# tricorder-teensy-mk-1_11.net
KiCad netlist of a schematic drawn in EAGLE
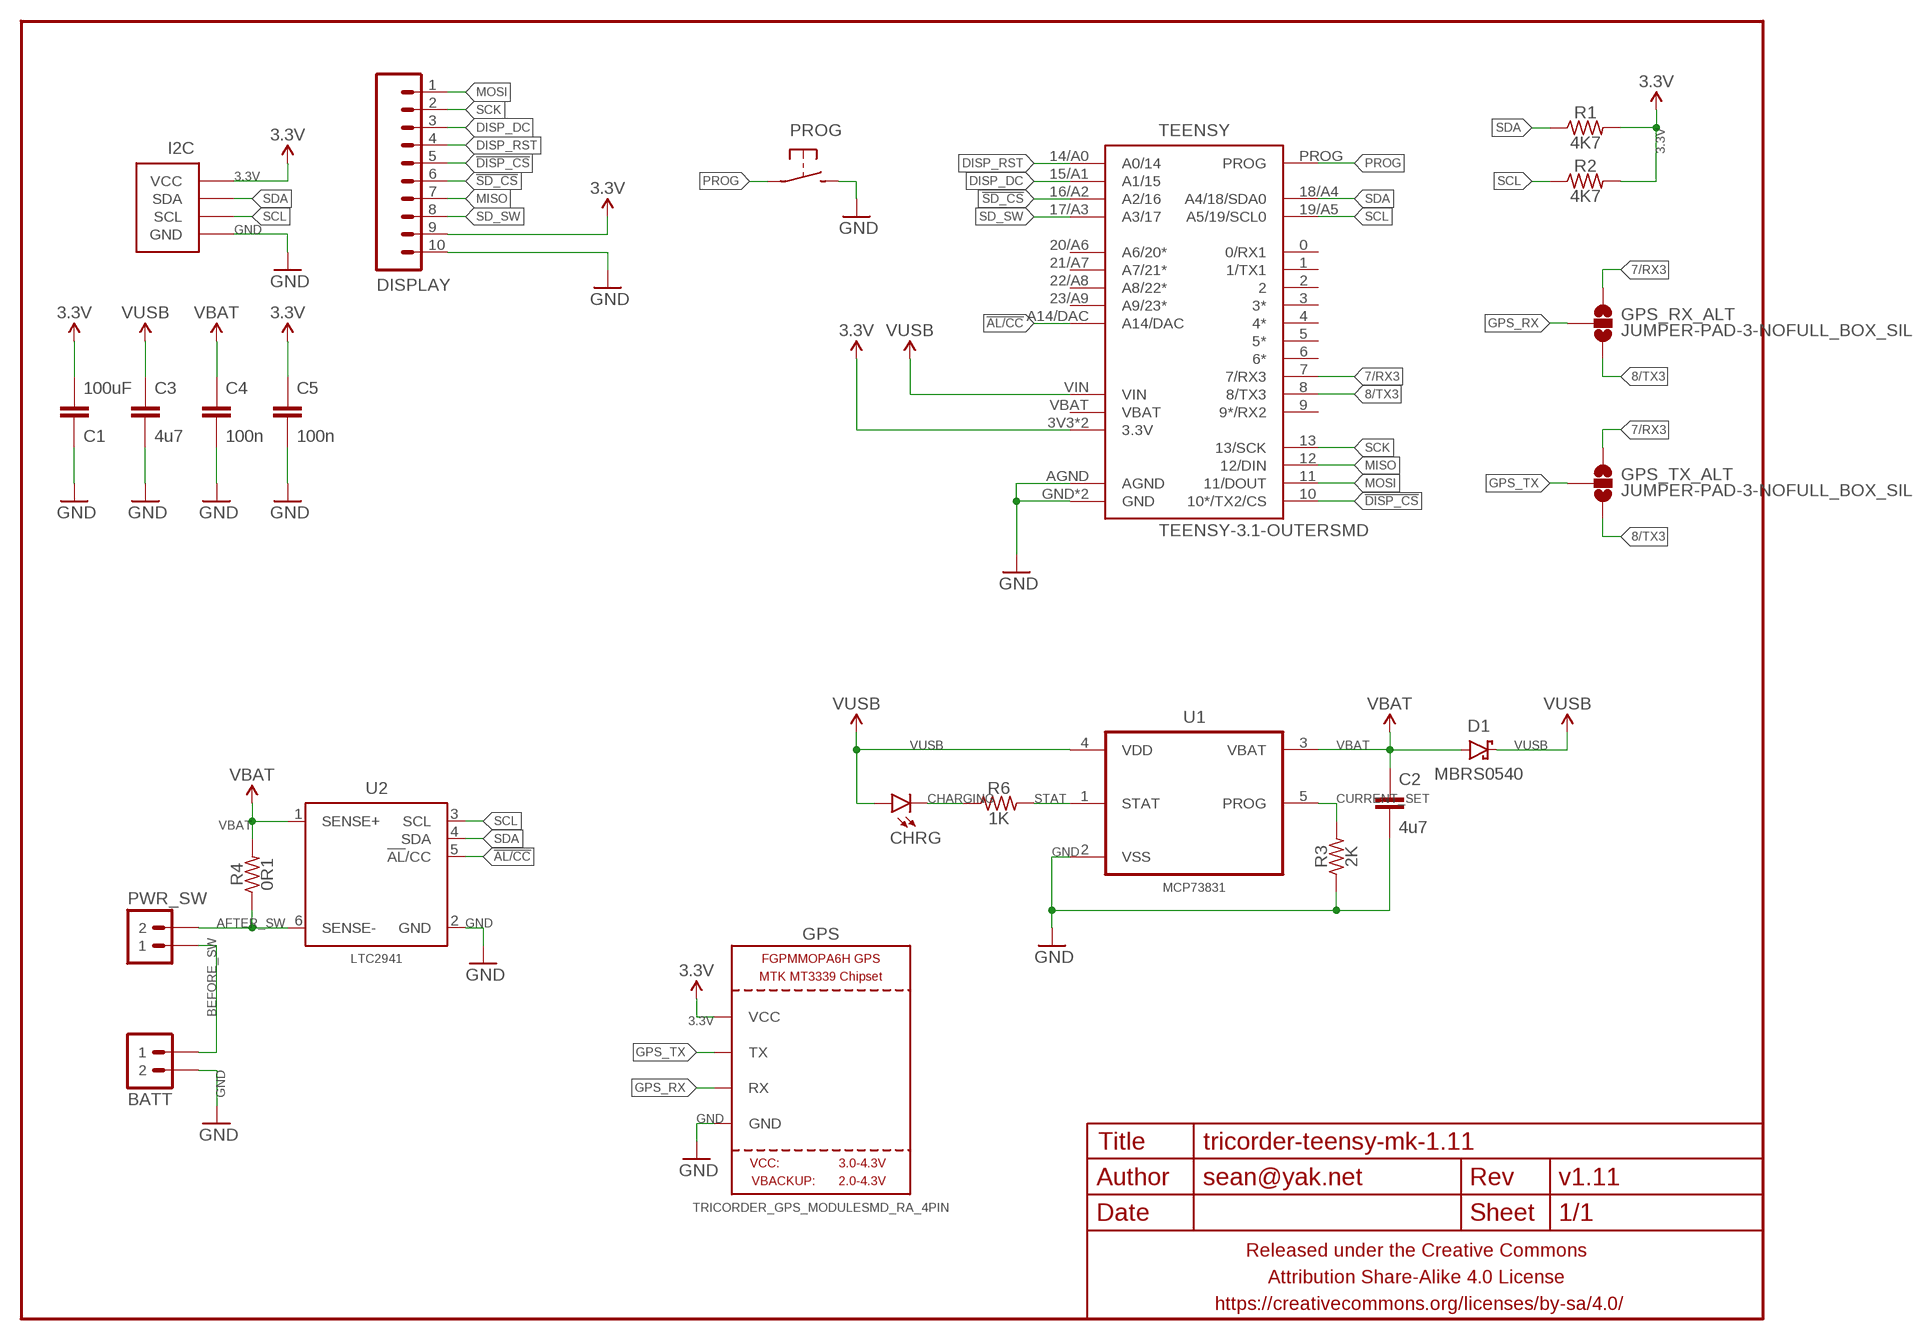
[diagram p0: schematic, sheet 1]

(export (version "E")
  (design (tool "Eeschema 10.0.6"))
  (components
    (comp (ref "BATT")
      (value "M02JST-2MM-SMT")
      (footprint "eagle-import:JST-2-SMD")
      (libsource (lib "eagle-import") (part "M02JST-2MM-SMT"))
    )
    (comp (ref "C1")
      (value "100uF")
      (footprint "eagle-import:C1210")
      (libsource (lib "eagle-import") (part "CAPACITOR-CERAMICC1210"))
    )
    (comp (ref "C2")
      (value "4u7")
      (footprint "eagle-import:C0603-TIGHTER")
      (libsource (lib "eagle-import") (part "CAPACITOR-CERAMICC0603-TIGHTER"))
    )
    (comp (ref "C3")
      (value "4u7")
      (footprint "eagle-import:C0603-TIGHTER")
      (libsource (lib "eagle-import") (part "CAPACITOR-CERAMICC0603-TIGHTER"))
    )
    (comp (ref "C4")
      (value "100n")
      (footprint "eagle-import:C0603-TIGHTER")
      (libsource (lib "eagle-import") (part "CAPACITOR-CERAMICC0603-TIGHTER"))
    )
    (comp (ref "C5")
      (value "100n")
      (footprint "eagle-import:C0603-TIGHTER")
      (libsource (lib "eagle-import") (part "CAPACITOR-CERAMICC0603-TIGHTER"))
    )
    (comp (ref "CHRG")
      (value "LED0603-TIGHT")
      (footprint "eagle-import:LED-0603-TIGHT")
      (libsource (lib "eagle-import") (part "LED0603-TIGHT"))
    )
    (comp (ref "D1")
      (value "MBRS0540")
      (footprint "eagle-import:SOD123-SCHOTTKY")
      (libsource (lib "eagle-import") (part "DIODE-SCHOTTKYSOD123"))
    )
    (comp (ref "DISPLAY")
      (value "M10SMD_RA_2MM")
      (footprint "eagle-import:1X10_SMD_RA_MALE")
      (libsource (lib "eagle-import") (part "M10SMD_RA_2MM"))
    )
    (comp (ref "FRAME1")
      (value "FRAME-LETTERNO_PACKAGE")
      (footprint "eagle-import:DUMMY")
      (fields
        (field (name "DESIGNER") "sean@yak.net")
        (field (name "VERSION") "v1.11")
        (field (name "DESIGNER_1") "sean@yak.net")
        (field (name "VERSION_1") "v1.11")
      )
      (libsource (lib "eagle-import") (part "FRAME-LETTERNO_PACKAGE"))
    )
    (comp (ref "GPS")
      (value "TRICORDER_GPS_MODULESMD_RA_4PIN")
      (footprint "eagle-import:TRICORDER_GPS_MODULE_RA_CONN_SMD_4PIN")
      (libsource (lib "eagle-import") (part "TRICORDER_GPS_MODULESMD_RA_4PIN"))
    )
    (comp (ref "GPS_RX_ALT")
      (value "JUMPER-PAD-3-NOFULL_BOX_SILK")
      (footprint "eagle-import:PAD-JUMPER-3-NO_YES_SILK_FULL_BOX")
      (libsource (lib "eagle-import") (part "JUMPER-PAD-3-NOFULL_BOX_SILK"))
    )
    (comp (ref "GPS_TX_ALT")
      (value "JUMPER-PAD-3-NOFULL_BOX_SILK")
      (footprint "eagle-import:PAD-JUMPER-3-NO_YES_SILK_FULL_BOX")
      (libsource (lib "eagle-import") (part "JUMPER-PAD-3-NOFULL_BOX_SILK"))
    )
    (comp (ref "I2C")
      (value "M04-I2CSMD_2MM_RA")
      (footprint "eagle-import:1X04_SMD_RA_2MM_I2C")
      (libsource (lib "eagle-import") (part "M04-I2CSMD_2MM_RA"))
    )
    (comp (ref "PROG")
      (value "SPST-NO-TACTCK-PTS840-GK")
      (footprint "eagle-import:TACTILE-SMD-CK-PTS840-GK")
      (libsource (lib "eagle-import") (part "SPST-NO-TACTCK-PTS840-GK"))
    )
    (comp (ref "PWR_SW")
      (value "M02JST-2MM-SMT")
      (footprint "eagle-import:JST-2-SMD")
      (libsource (lib "eagle-import") (part "M02JST-2MM-SMT"))
    )
    (comp (ref "R1")
      (value "4K7")
      (footprint "eagle-import:R0603-TIGHTER")
      (libsource (lib "eagle-import") (part "RESISTORR0603-TIGHTER"))
    )
    (comp (ref "R2")
      (value "4K7")
      (footprint "eagle-import:R0603-TIGHTER")
      (libsource (lib "eagle-import") (part "RESISTORR0603-TIGHTER"))
    )
    (comp (ref "R3")
      (value "2K")
      (footprint "eagle-import:R0603-TIGHTER")
      (libsource (lib "eagle-import") (part "RESISTORR0603-TIGHTER"))
    )
    (comp (ref "R4")
      (value "0R1")
      (footprint "eagle-import:R0805-TIGHTER")
      (libsource (lib "eagle-import") (part "RESISTORR0805-TIGHTER"))
    )
    (comp (ref "R6")
      (value "1K")
      (footprint "eagle-import:R0603-TIGHTER")
      (libsource (lib "eagle-import") (part "RESISTORR0603-TIGHTER"))
    )
    (comp (ref "TEENSY")
      (value "TEENSY-3.1-OUTERSMD")
      (footprint "eagle-import:TEENSY-3.1_SMT_BOTTOM_OUTERONLY")
      (libsource (lib "eagle-import") (part "TEENSY-3.1-OUTERSMD"))
    )
    (comp (ref "U1")
      (value "MCP73831")
      (footprint "eagle-import:SOT95P280X145-5N")
      (fields (field (name "MPN") "MCP73831T-2ACI/OT"))
      (libsource (lib "eagle-import") (part "MCP73831T-2ACI/OT"))
    )
    (comp (ref "U2")
      (value "LTC2941")
      (footprint "eagle-import:DFN200X300X50-7N")
      (libsource (lib "eagle-import") (part "LTC2941/2DCB"))
    )
  )
  (nets
    (net (code "1") (name "/AFTER_SW") (class "Default")
      (node (ref "PWR_SW") (pin "1") (pinfunction "2_1") (pintype "passive"))
      (node (ref "R4") (pin "1") (pinfunction "1_1") (pintype "passive"))
      (node (ref "U2") (pin "6") (pinfunction "SENSE-_6") (pintype "bidirectional"))
    )
    (net (code "2") (name "/BEFORE_SW") (class "Default")
      (node (ref "BATT") (pin "2") (pinfunction "1_2") (pintype "passive"))
      (node (ref "PWR_SW") (pin "2") (pinfunction "1_2") (pintype "passive"))
    )
    (net (code "3") (name "/CHARGING") (class "Default")
      (node (ref "CHRG") (pin "C") (pinfunction "C_C") (pintype "passive"))
      (node (ref "R6") (pin "1") (pinfunction "1_1") (pintype "passive"))
    )
    (net (code "4") (name "/CURRENT_SET") (class "Default")
      (node (ref "R3") (pin "2") (pinfunction "2_2") (pintype "passive"))
      (node (ref "U1") (pin "5") (pinfunction "PROG_5") (pintype "input"))
    )
    (net (code "5") (name "/STAT") (class "Default")
      (node (ref "R6") (pin "2") (pinfunction "2_2") (pintype "passive"))
      (node (ref "U1") (pin "1") (pinfunction "STAT_1") (pintype "output"))
    )
    (net (code "6") (name "/~{AL{slash}CC}") (class "Default")
      (node (ref "TEENSY") (pin "A14/DAC") (pinfunction "A14/DAC_A14/DAC") (pintype "bidirectional"))
      (node (ref "U2") (pin "5") (pinfunction "~{AL}/CC_5") (pintype "bidirectional"))
    )
    (net (code "7") (name "/~{DISP_CS}") (class "Default")
      (node (ref "DISPLAY") (pin "5") (pinfunction "5_5") (pintype "passive"))
      (node (ref "TEENSY") (pin "10") (pinfunction "10*/TX2/CS_10") (pintype "bidirectional"))
    )
    (net (code "8") (name "/~{SD_CS}") (class "Default")
      (node (ref "DISPLAY") (pin "6") (pinfunction "6_6") (pintype "passive"))
      (node (ref "TEENSY") (pin "16/A2") (pinfunction "A2/16_16/A2") (pintype "bidirectional"))
    )
    (net (code "9") (name "3.3V") (class "Default")
      (node (ref "C1") (pin "2") (pinfunction "2_2") (pintype "passive"))
      (node (ref "C5") (pin "1") (pinfunction "1_1") (pintype "passive"))
      (node (ref "DISPLAY") (pin "9") (pinfunction "9_9") (pintype "passive"))
      (node (ref "GPS") (pin "VCC") (pinfunction "VCC_VCC") (pintype "bidirectional"))
      (node (ref "I2C") (pin "VCC") (pinfunction "VCC_VCC") (pintype "bidirectional"))
      (node (ref "R1") (pin "2") (pinfunction "2_2") (pintype "passive"))
      (node (ref "R2") (pin "2") (pinfunction "2_2") (pintype "passive"))
      (node (ref "TEENSY") (pin "3V3") (pinfunction "3.3V_3V3") (pintype "bidirectional"))
      (node (ref "TEENSY") (pin "3V3@1") (pinfunction "3.3V_3V3@1") (pintype "bidirectional"))
    )
    (net (code "10") (name "7{slash}RX3") (class "Default")
      (node (ref "GPS_RX_ALT") (pin "1") (pinfunction "1_1") (pintype "passive"))
      (node (ref "GPS_TX_ALT") (pin "1") (pinfunction "1_1") (pintype "passive"))
      (node (ref "TEENSY") (pin "7") (pinfunction "7/RX3_7") (pintype "bidirectional"))
    )
    (net (code "11") (name "8{slash}TX3") (class "Default")
      (node (ref "GPS_RX_ALT") (pin "3") (pinfunction "3_3") (pintype "passive"))
      (node (ref "GPS_TX_ALT") (pin "3") (pinfunction "3_3") (pintype "passive"))
      (node (ref "TEENSY") (pin "8") (pinfunction "8/TX3_8") (pintype "bidirectional"))
    )
    (net (code "12") (name "DISP_DC") (class "Default")
      (node (ref "DISPLAY") (pin "3") (pinfunction "3_3") (pintype "passive"))
      (node (ref "TEENSY") (pin "15/A1") (pinfunction "A1/15_15/A1") (pintype "bidirectional"))
    )
    (net (code "13") (name "DISP_RST") (class "Default")
      (node (ref "DISPLAY") (pin "4") (pinfunction "4_4") (pintype "passive"))
      (node (ref "TEENSY") (pin "14/A0") (pinfunction "A0/14_14/A0") (pintype "bidirectional"))
    )
    (net (code "14") (name "GND") (class "Default")
      (node (ref "BATT") (pin "1") (pinfunction "2_1") (pintype "passive"))
      (node (ref "C1") (pin "1") (pinfunction "1_1") (pintype "passive"))
      (node (ref "C2") (pin "2") (pinfunction "2_2") (pintype "passive"))
      (node (ref "C3") (pin "2") (pinfunction "2_2") (pintype "passive"))
      (node (ref "C4") (pin "2") (pinfunction "2_2") (pintype "passive"))
      (node (ref "C5") (pin "2") (pinfunction "2_2") (pintype "passive"))
      (node (ref "DISPLAY") (pin "10") (pinfunction "10_10") (pintype "passive"))
      (node (ref "GPS") (pin "GND") (pinfunction "GND_GND") (pintype "bidirectional"))
      (node (ref "I2C") (pin "GND") (pinfunction "GND_GND") (pintype "bidirectional"))
      (node (ref "PROG") (pin "3") (pinfunction "2_3") (pintype "passive"))
      (node (ref "PROG") (pin "4") (pinfunction "2_4") (pintype "passive"))
      (node (ref "R3") (pin "1") (pinfunction "1_1") (pintype "passive"))
      (node (ref "TEENSY") (pin "AGND") (pinfunction "AGND_AGND") (pintype "bidirectional"))
      (node (ref "TEENSY") (pin "GND") (pinfunction "GND_GND") (pintype "bidirectional"))
      (node (ref "TEENSY") (pin "GND@1") (pinfunction "GND_GND@1") (pintype "bidirectional"))
      (node (ref "U1") (pin "2") (pinfunction "VSS_2") (pintype "power_in"))
      (node (ref "U2") (pin "2") (pinfunction "GND_2") (pintype "bidirectional"))
    )
    (net (code "15") (name "GPS_RX") (class "Default")
      (node (ref "GPS") (pin "RX") (pinfunction "RX_RX") (pintype "bidirectional"))
      (node (ref "GPS_RX_ALT") (pin "2") (pinfunction "2_2") (pintype "passive"))
    )
    (net (code "16") (name "GPS_TX") (class "Default")
      (node (ref "GPS") (pin "TX") (pinfunction "TX_TX") (pintype "bidirectional"))
      (node (ref "GPS_TX_ALT") (pin "2") (pinfunction "2_2") (pintype "passive"))
    )
    (net (code "17") (name "MISO") (class "Default")
      (node (ref "DISPLAY") (pin "7") (pinfunction "7_7") (pintype "passive"))
      (node (ref "TEENSY") (pin "12") (pinfunction "12/DIN_12") (pintype "bidirectional"))
    )
    (net (code "18") (name "MOSI") (class "Default")
      (node (ref "DISPLAY") (pin "1") (pinfunction "1_1") (pintype "passive"))
      (node (ref "TEENSY") (pin "11") (pinfunction "11/DOUT_11") (pintype "bidirectional"))
    )
    (net (code "19") (name "PROG") (class "Default")
      (node (ref "PROG") (pin "1") (pinfunction "1_1") (pintype "passive"))
      (node (ref "PROG") (pin "2") (pinfunction "1_2") (pintype "passive"))
      (node (ref "TEENSY") (pin "PROG") (pinfunction "PROG_PROG") (pintype "bidirectional"))
    )
    (net (code "20") (name "SCK") (class "Default")
      (node (ref "DISPLAY") (pin "2") (pinfunction "2_2") (pintype "passive"))
      (node (ref "TEENSY") (pin "13") (pinfunction "13/SCK_13") (pintype "bidirectional"))
    )
    (net (code "21") (name "SCL") (class "Default")
      (node (ref "I2C") (pin "SCL") (pinfunction "SCL_SCL") (pintype "bidirectional"))
      (node (ref "R2") (pin "1") (pinfunction "1_1") (pintype "passive"))
      (node (ref "TEENSY") (pin "19/A5") (pinfunction "A5/19/SCL0_19/A5") (pintype "bidirectional"))
      (node (ref "U2") (pin "3") (pinfunction "SCL_3") (pintype "bidirectional"))
    )
    (net (code "22") (name "SDA") (class "Default")
      (node (ref "I2C") (pin "SDA") (pinfunction "SDA_SDA") (pintype "bidirectional"))
      (node (ref "R1") (pin "1") (pinfunction "1_1") (pintype "passive"))
      (node (ref "TEENSY") (pin "18/A4") (pinfunction "A4/18/SDA0_18/A4") (pintype "bidirectional"))
      (node (ref "U2") (pin "4") (pinfunction "SDA_4") (pintype "bidirectional"))
    )
    (net (code "23") (name "SD_SW") (class "Default")
      (node (ref "DISPLAY") (pin "8") (pinfunction "8_8") (pintype "passive"))
      (node (ref "TEENSY") (pin "17/A3") (pinfunction "A3/17_17/A3") (pintype "bidirectional"))
    )
    (net (code "24") (name "VBAT") (class "Default")
      (node (ref "C2") (pin "1") (pinfunction "1_1") (pintype "passive"))
      (node (ref "C4") (pin "1") (pinfunction "1_1") (pintype "passive"))
      (node (ref "D1") (pin "A") (pinfunction "A_A") (pintype "passive"))
      (node (ref "R4") (pin "2") (pinfunction "2_2") (pintype "passive"))
      (node (ref "U1") (pin "3") (pinfunction "VBAT_3") (pintype "output"))
      (node (ref "U2") (pin "1") (pinfunction "SENSE+_1") (pintype "bidirectional"))
    )
    (net (code "25") (name "VUSB") (class "Default")
      (node (ref "C3") (pin "1") (pinfunction "1_1") (pintype "passive"))
      (node (ref "CHRG") (pin "A") (pinfunction "A_A") (pintype "passive"))
      (node (ref "D1") (pin "C") (pinfunction "C_C") (pintype "passive"))
      (node (ref "TEENSY") (pin "VIN") (pinfunction "VIN_VIN") (pintype "bidirectional"))
      (node (ref "U1") (pin "4") (pinfunction "VDD_4") (pintype "power_in"))
    )
    (net (code "26") (name "unconnected-(TEENSY-0{slash}RX1-Pad0)") (class "Default")
      (node (ref "TEENSY") (pin "0") (pinfunction "0/RX1_0") (pintype "bidirectional"))
    )
    (net (code "27") (name "unconnected-(TEENSY-1{slash}TX1-Pad1)") (class "Default")
      (node (ref "TEENSY") (pin "1") (pinfunction "1/TX1_1") (pintype "bidirectional"))
    )
    (net (code "28") (name "unconnected-(TEENSY-3*-Pad3)") (class "Default")
      (node (ref "TEENSY") (pin "3") (pinfunction "3*_3") (pintype "bidirectional"))
    )
    (net (code "29") (name "unconnected-(TEENSY-4*-Pad4)") (class "Default")
      (node (ref "TEENSY") (pin "4") (pinfunction "4*_4") (pintype "bidirectional"))
    )
    (net (code "30") (name "unconnected-(TEENSY-5*-Pad5)") (class "Default")
      (node (ref "TEENSY") (pin "5") (pinfunction "5*_5") (pintype "bidirectional"))
    )
    (net (code "31") (name "unconnected-(TEENSY-6*-Pad6)") (class "Default")
      (node (ref "TEENSY") (pin "6") (pinfunction "6*_6") (pintype "bidirectional"))
    )
    (net (code "32") (name "unconnected-(TEENSY-9*{slash}RX2-Pad9)") (class "Default")
      (node (ref "TEENSY") (pin "9") (pinfunction "9*/RX2_9") (pintype "bidirectional"))
    )
    (net (code "33") (name "unconnected-(TEENSY-A6{slash}20*-Pad20{slash}A6)") (class "Default")
      (node (ref "TEENSY") (pin "20/A6") (pinfunction "A6/20*_20/A6") (pintype "bidirectional"))
    )
    (net (code "34") (name "unconnected-(TEENSY-A7{slash}21*-Pad21{slash}A7)") (class "Default")
      (node (ref "TEENSY") (pin "21/A7") (pinfunction "A7/21*_21/A7") (pintype "bidirectional"))
    )
    (net (code "35") (name "unconnected-(TEENSY-A8{slash}22*-Pad22{slash}A8)") (class "Default")
      (node (ref "TEENSY") (pin "22/A8") (pinfunction "A8/22*_22/A8") (pintype "bidirectional"))
    )
    (net (code "36") (name "unconnected-(TEENSY-A9{slash}23*-Pad23{slash}A9)") (class "Default")
      (node (ref "TEENSY") (pin "23/A9") (pinfunction "A9/23*_23/A9") (pintype "bidirectional"))
    )
    (net (code "37") (name "unconnected-(TEENSY-Pad2)") (class "Default")
      (node (ref "TEENSY") (pin "2") (pinfunction "2_2") (pintype "bidirectional"))
    )
    (net (code "38") (name "unconnected-(TEENSY-PadVBAT)") (class "Default")
      (node (ref "TEENSY") (pin "VBAT") (pinfunction "VBAT_VBAT") (pintype "bidirectional"))
    )
  )
)
